# led.net
KiCad netlist of a schematic drawn in Altium Designer
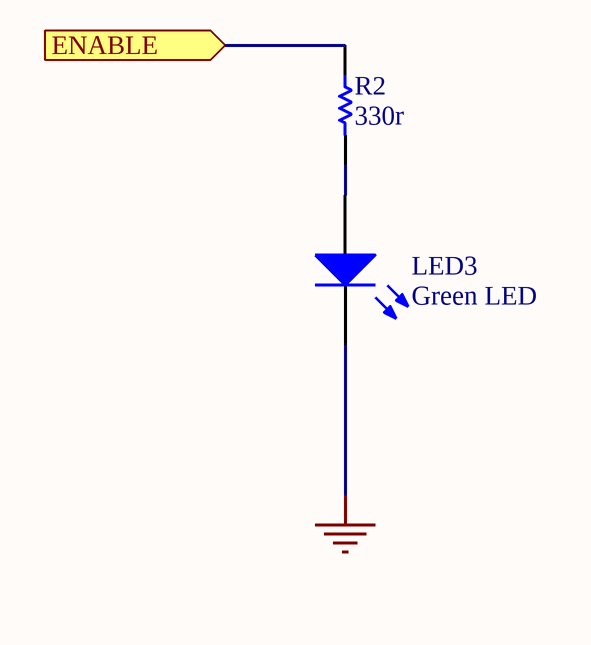
[diagram p0: led.SchDoc]

(export (version "E")
  (design (tool "Eeschema 10.0.6"))
  (components
    (comp (ref "LED3")
      (value "Green LED")
      (footprint "TP2_PcbLib:LED 0805")
      (description "Typical RED, GREEN, YELLOW, AMBER GaAs LED")
      (fields (field (name "PUBLISHER") "Altium Limited"))
      (libsource (lib "Miscellaneous Devices") (part "LED2"))
    )
    (comp (ref "R2")
      (value "330r")
      (footprint "TP2_PcbLib:RESC1608N")
      (description "Resistor")
      (fields (field (name "PUBLISHER") "Altium Limited"))
      (libsource (lib "Miscellaneous Devices") (part "Res1"))
    )
  )
  (nets
    (net (code "1") (name "/ENABLE") (class "Default")
      (node (ref "R2") (pin "1") (pinfunction "1_1") (pintype "passive"))
    )
    (net (code "2") (name "GND") (class "Default")
      (node (ref "LED3") (pin "2") (pinfunction "K_2") (pintype "passive"))
    )
    (net (code "3") (name "Net-(LED3-A)") (class "Default")
      (node (ref "LED3") (pin "1") (pinfunction "A_1") (pintype "passive"))
      (node (ref "R2") (pin "2") (pinfunction "2_2") (pintype "passive"))
    )
  )
)
